# control-tu55v6.net
KiCad netlist of a schematic drawn in EAGLE
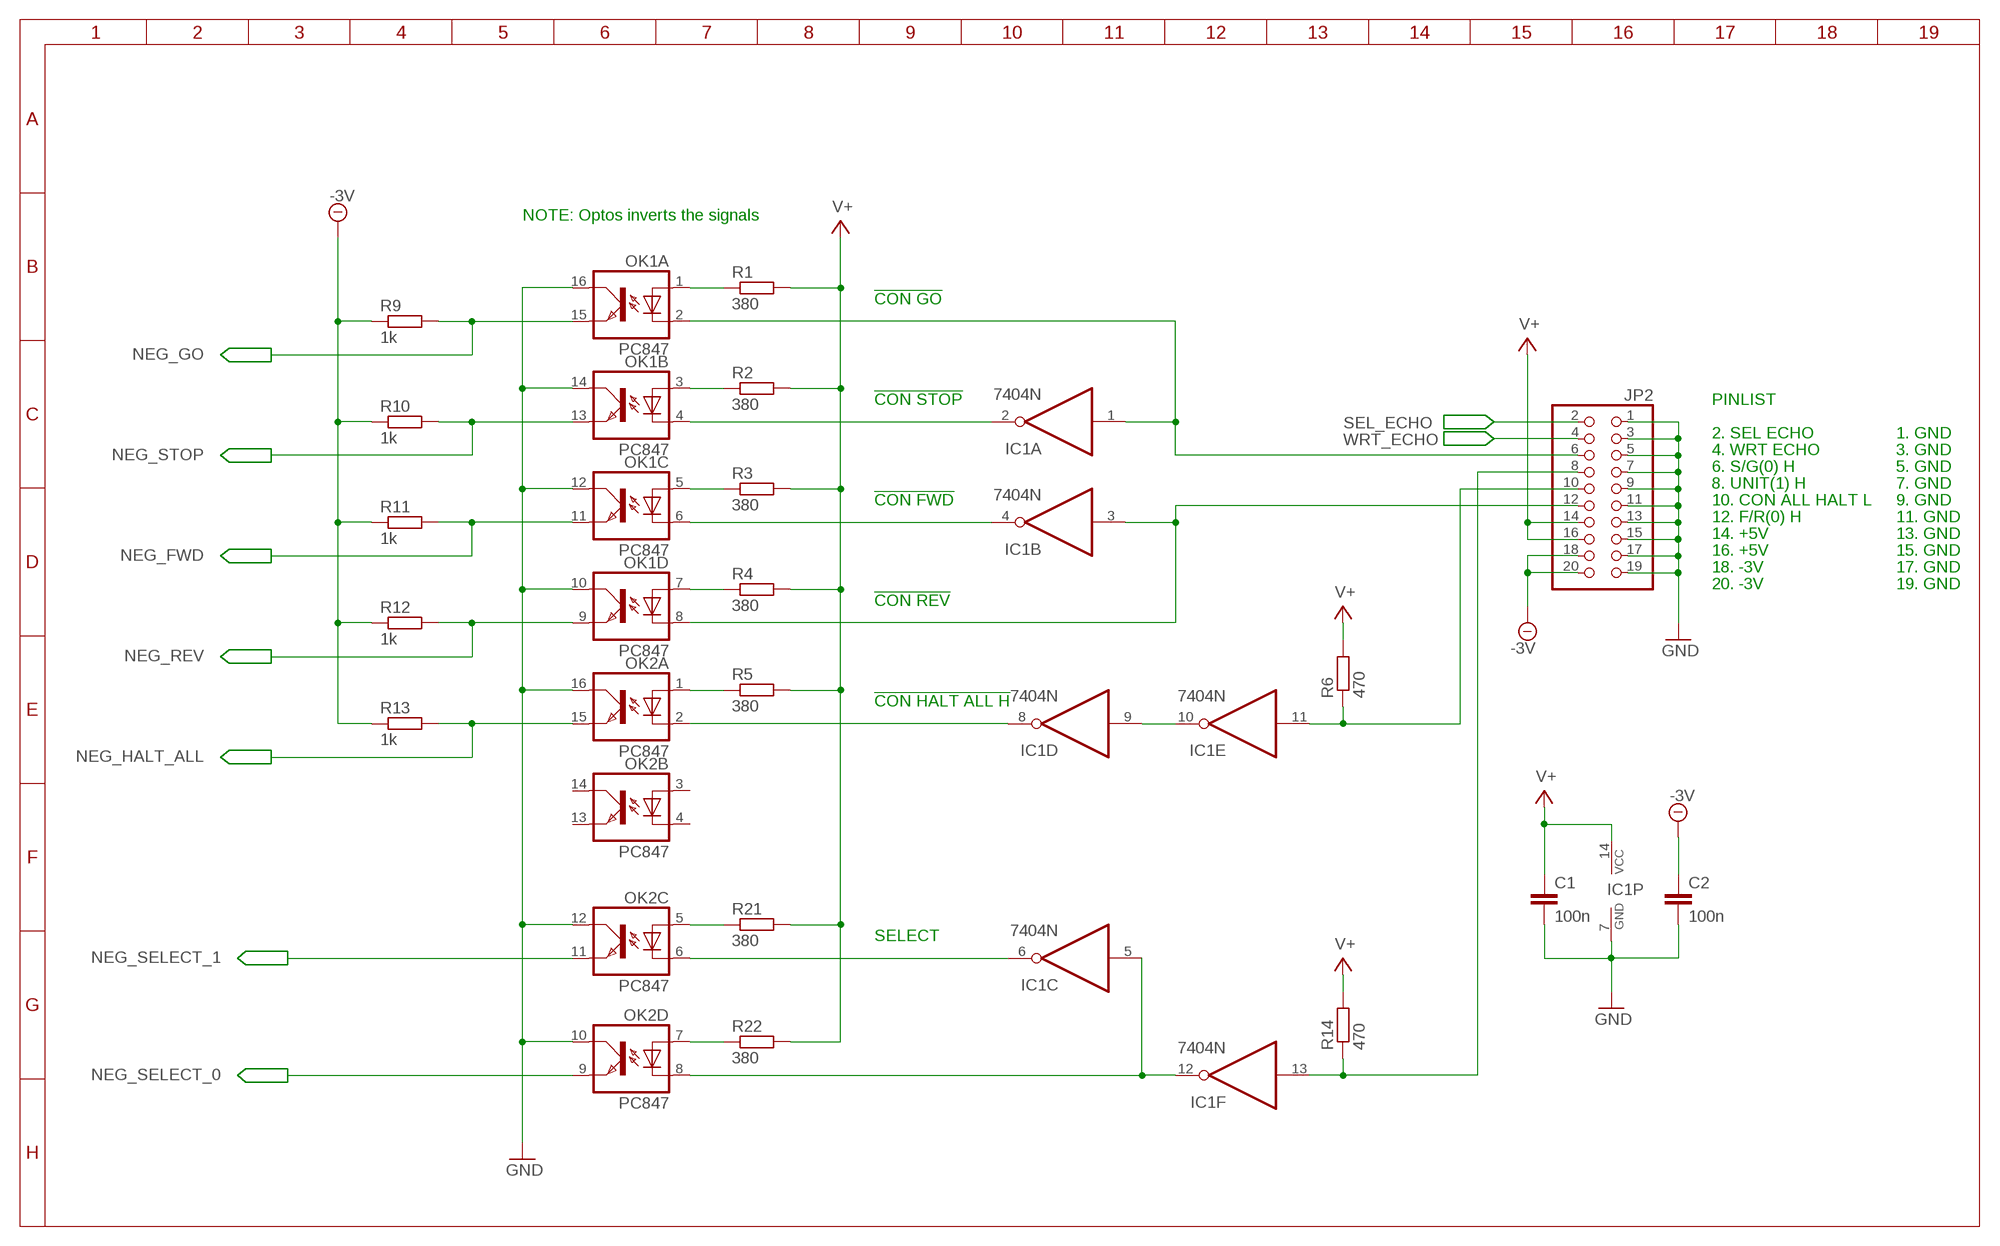
[diagram p0: schematic, sheet 1]
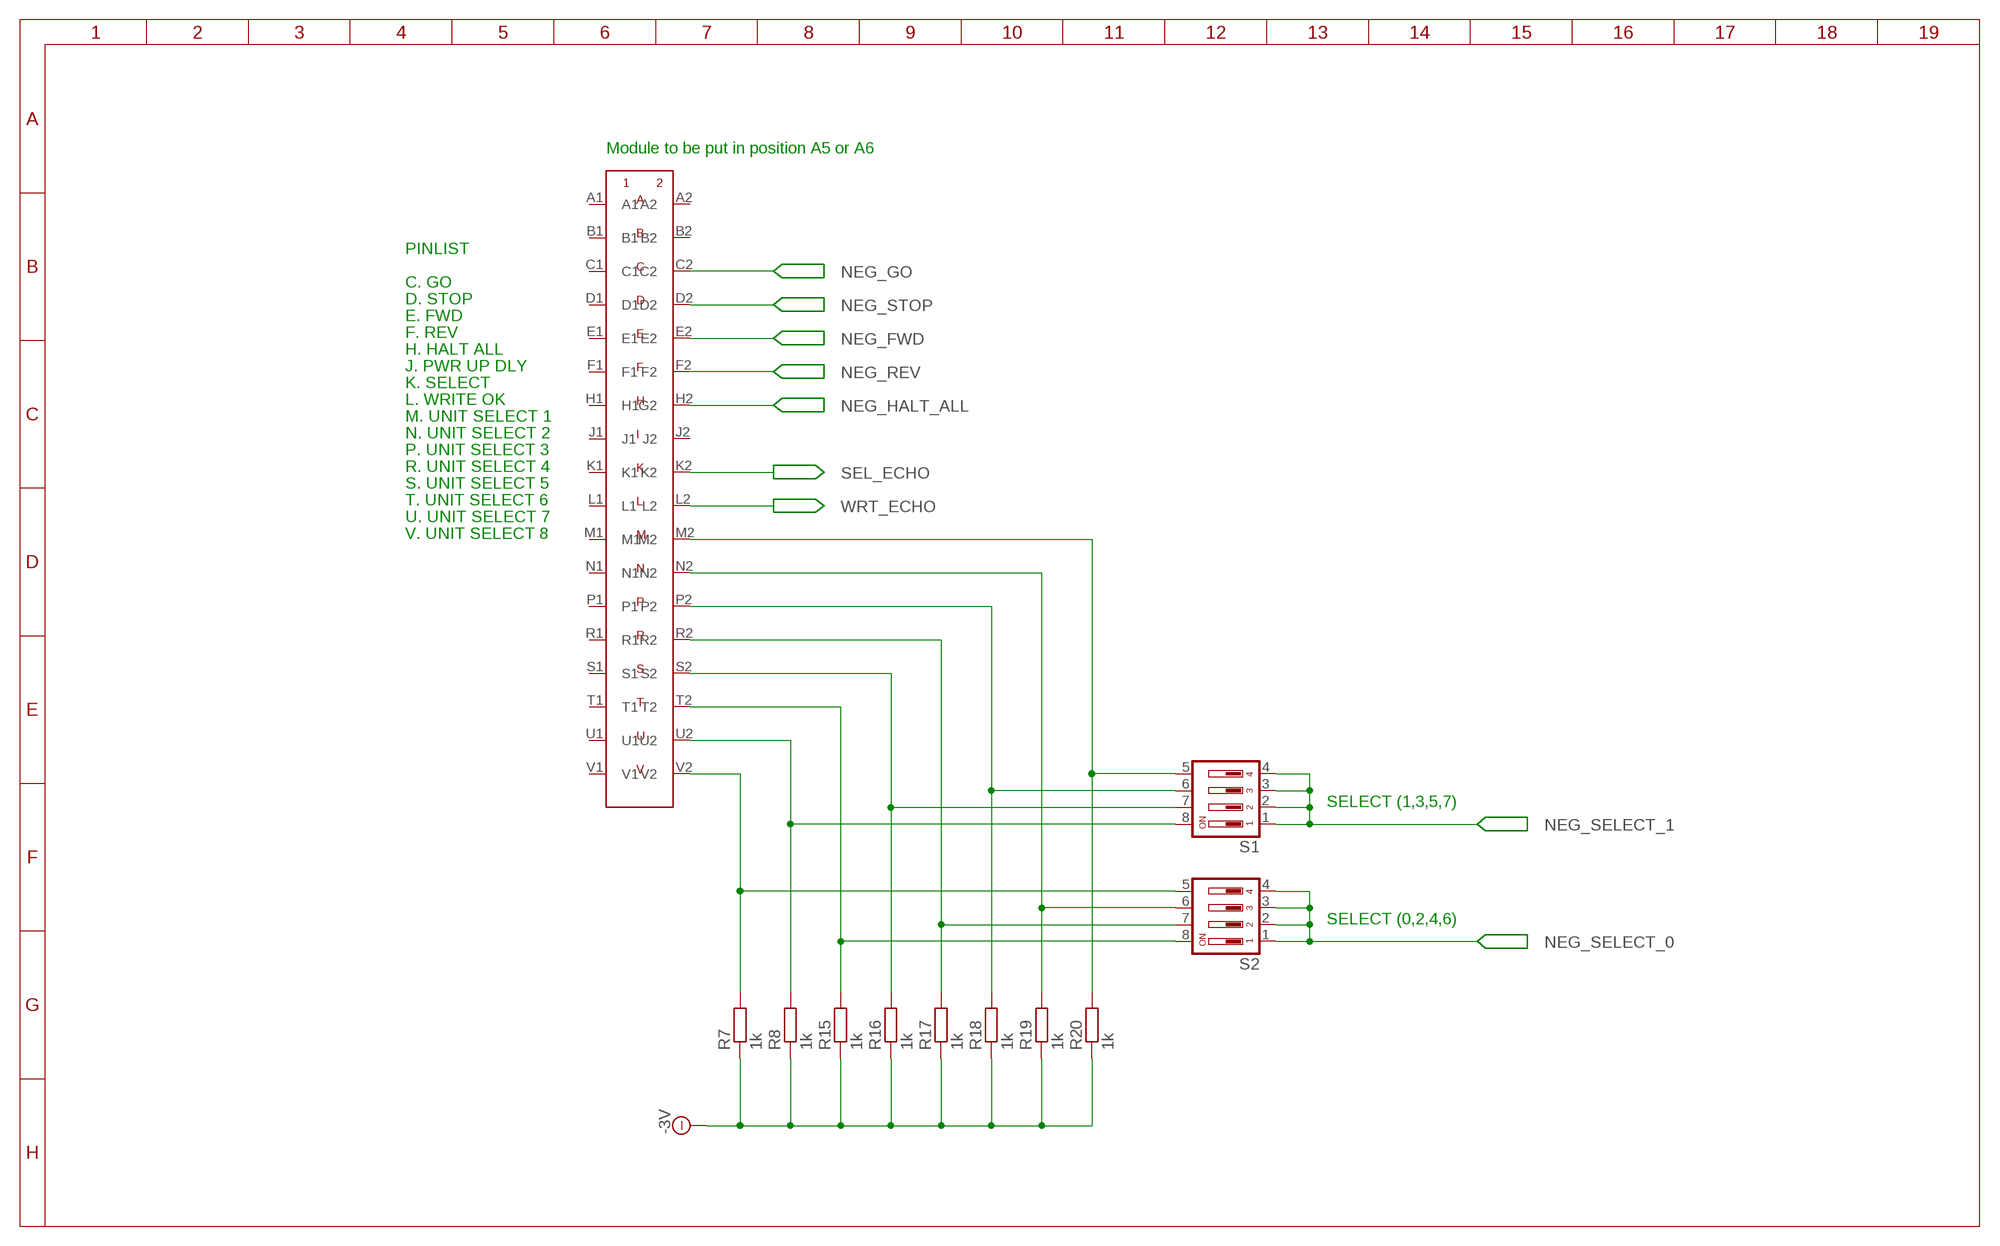
[diagram p1: schematic, sheet 2]

(export (version "E")
  (design (tool "Eeschema 10.0.6"))
  (components
    (comp (ref "C1")
      (value "100n")
      (footprint "eagle-import:C5B3.5")
      (libsource (lib "eagle-import") (part "C5/3.5"))
    )
    (comp (ref "C2")
      (value "100n")
      (footprint "eagle-import:C5B3.5")
      (libsource (lib "eagle-import") (part "C5/3.5"))
    )
    (comp (ref "IC1")
      (value "7404N")
      (footprint "eagle-import:DIL14")
      (libsource (lib "eagle-import") (part "7404N"))
    )
    (comp (ref "JP2")
      (value "PINHD-2X10/90-FRAMED")
      (footprint "eagle-import:2Z10_90-FRAMED")
      (libsource (lib "eagle-import") (part "PINHD-2X10/90-FRAMED"))
    )
    (comp (ref "OK1")
      (value "PC847")
      (footprint "eagle-import:DIL16")
      (libsource (lib "eagle-import") (part "PC847"))
    )
    (comp (ref "OK2")
      (value "PC847")
      (footprint "eagle-import:DIL16")
      (libsource (lib "eagle-import") (part "PC847"))
    )
    (comp (ref "R1")
      (value "380")
      (footprint "eagle-import:0207_10")
      (libsource (lib "eagle-import") (part "R-EU_0207/10"))
    )
    (comp (ref "R2")
      (value "380")
      (footprint "eagle-import:0207_10")
      (libsource (lib "eagle-import") (part "R-EU_0207/10"))
    )
    (comp (ref "R3")
      (value "380")
      (footprint "eagle-import:0207_10")
      (libsource (lib "eagle-import") (part "R-EU_0207/10"))
    )
    (comp (ref "R4")
      (value "380")
      (footprint "eagle-import:0207_10")
      (libsource (lib "eagle-import") (part "R-EU_0207/10"))
    )
    (comp (ref "R5")
      (value "380")
      (footprint "eagle-import:0207_10")
      (libsource (lib "eagle-import") (part "R-EU_0207/10"))
    )
    (comp (ref "R6")
      (value "470")
      (footprint "eagle-import:0207_10")
      (libsource (lib "eagle-import") (part "R-EU_0207/10"))
    )
    (comp (ref "R9")
      (value "1k")
      (footprint "eagle-import:0207_10")
      (libsource (lib "eagle-import") (part "R-EU_0207/10"))
    )
    (comp (ref "R10")
      (value "1k")
      (footprint "eagle-import:0207_10")
      (libsource (lib "eagle-import") (part "R-EU_0207/10"))
    )
    (comp (ref "R11")
      (value "1k")
      (footprint "eagle-import:0207_10")
      (libsource (lib "eagle-import") (part "R-EU_0207/10"))
    )
    (comp (ref "R12")
      (value "1k")
      (footprint "eagle-import:0207_10")
      (libsource (lib "eagle-import") (part "R-EU_0207/10"))
    )
    (comp (ref "R13")
      (value "1k")
      (footprint "eagle-import:0207_10")
      (libsource (lib "eagle-import") (part "R-EU_0207/10"))
    )
    (comp (ref "R14")
      (value "470")
      (footprint "eagle-import:0207_10")
      (libsource (lib "eagle-import") (part "R-EU_0207/10"))
    )
    (comp (ref "R21")
      (value "380")
      (footprint "eagle-import:0207_10")
      (libsource (lib "eagle-import") (part "R-EU_0207/10"))
    )
    (comp (ref "R22")
      (value "380")
      (footprint "eagle-import:0207_10")
      (libsource (lib "eagle-import") (part "R-EU_0207/10"))
    )
    (comp (ref "CON1")
      (value "FLIPCHIP_1NORMAL")
      (footprint "eagle-import:FLIPCHIP-1")
      (libsource (lib "eagle-import") (part "FLIPCHIP_1NORMAL"))
    )
    (comp (ref "R7")
      (value "1k")
      (footprint "eagle-import:0207_10")
      (libsource (lib "eagle-import") (part "R-EU_0207/10"))
    )
    (comp (ref "R8")
      (value "1k")
      (footprint "eagle-import:0207_10")
      (libsource (lib "eagle-import") (part "R-EU_0207/10"))
    )
    (comp (ref "R15")
      (value "1k")
      (footprint "eagle-import:0207_10")
      (libsource (lib "eagle-import") (part "R-EU_0207/10"))
    )
    (comp (ref "R16")
      (value "1k")
      (footprint "eagle-import:0207_10")
      (libsource (lib "eagle-import") (part "R-EU_0207/10"))
    )
    (comp (ref "R17")
      (value "1k")
      (footprint "eagle-import:0207_10")
      (libsource (lib "eagle-import") (part "R-EU_0207/10"))
    )
    (comp (ref "R18")
      (value "1k")
      (footprint "eagle-import:0207_10")
      (libsource (lib "eagle-import") (part "R-EU_0207/10"))
    )
    (comp (ref "R19")
      (value "1k")
      (footprint "eagle-import:0207_10")
      (libsource (lib "eagle-import") (part "R-EU_0207/10"))
    )
    (comp (ref "R20")
      (value "1k")
      (footprint "eagle-import:0207_10")
      (libsource (lib "eagle-import") (part "R-EU_0207/10"))
    )
    (comp (ref "S1")
      (value "DIP04YL")
      (footprint "eagle-import:DIP04YL")
      (libsource (lib "eagle-import") (part "DIP04YL"))
    )
    (comp (ref "S2")
      (value "DIP04YL")
      (footprint "eagle-import:DIP04YL")
      (libsource (lib "eagle-import") (part "DIP04YL"))
    )
  )
  (nets
    (net (code "1") (name "-3V") (class "Default")
      (node (ref "C2") (pin "1") (pinfunction "1_1") (pintype "passive"))
      (node (ref "JP2") (pin "18") (pinfunction "18_18") (pintype "passive"))
      (node (ref "JP2") (pin "20") (pinfunction "20_20") (pintype "passive"))
      (node (ref "R10") (pin "1") (pinfunction "1_1") (pintype "passive"))
      (node (ref "R11") (pin "1") (pinfunction "1_1") (pintype "passive"))
      (node (ref "R12") (pin "1") (pinfunction "1_1") (pintype "passive"))
      (node (ref "R13") (pin "1") (pinfunction "1_1") (pintype "passive"))
      (node (ref "R15") (pin "1") (pinfunction "1_1") (pintype "passive"))
      (node (ref "R16") (pin "1") (pinfunction "1_1") (pintype "passive"))
      (node (ref "R17") (pin "1") (pinfunction "1_1") (pintype "passive"))
      (node (ref "R18") (pin "1") (pinfunction "1_1") (pintype "passive"))
      (node (ref "R19") (pin "1") (pinfunction "1_1") (pintype "passive"))
      (node (ref "R20") (pin "1") (pinfunction "1_1") (pintype "passive"))
      (node (ref "R7") (pin "1") (pinfunction "1_1") (pintype "passive"))
      (node (ref "R8") (pin "1") (pinfunction "1_1") (pintype "passive"))
      (node (ref "R9") (pin "1") (pinfunction "1_1") (pintype "passive"))
    )
    (net (code "2") (name "GND") (class "Default")
      (node (ref "C1") (pin "2") (pinfunction "2_2") (pintype "passive"))
      (node (ref "C2") (pin "2") (pinfunction "2_2") (pintype "passive"))
      (node (ref "IC1") (pin "7") (pinfunction "GND_7") (pintype "power_in"))
      (node (ref "JP2") (pin "1") (pinfunction "1_1") (pintype "passive"))
      (node (ref "JP2") (pin "11") (pinfunction "11_11") (pintype "passive"))
      (node (ref "JP2") (pin "13") (pinfunction "13_13") (pintype "passive"))
      (node (ref "JP2") (pin "15") (pinfunction "15_15") (pintype "passive"))
      (node (ref "JP2") (pin "17") (pinfunction "17_17") (pintype "passive"))
      (node (ref "JP2") (pin "19") (pinfunction "19_19") (pintype "passive"))
      (node (ref "JP2") (pin "3") (pinfunction "3_3") (pintype "passive"))
      (node (ref "JP2") (pin "5") (pinfunction "5_5") (pintype "passive"))
      (node (ref "JP2") (pin "7") (pinfunction "7_7") (pintype "passive"))
      (node (ref "JP2") (pin "9") (pinfunction "9_9") (pintype "passive"))
      (node (ref "OK1") (pin "10") (pinfunction "COL_10") (pintype "passive"))
      (node (ref "OK1") (pin "12") (pinfunction "COL_12") (pintype "passive"))
      (node (ref "OK1") (pin "14") (pinfunction "COL_14") (pintype "passive"))
      (node (ref "OK1") (pin "16") (pinfunction "COL_16") (pintype "passive"))
      (node (ref "OK2") (pin "10") (pinfunction "COL_10") (pintype "passive"))
      (node (ref "OK2") (pin "12") (pinfunction "COL_12") (pintype "passive"))
      (node (ref "OK2") (pin "16") (pinfunction "COL_16") (pintype "passive"))
    )
    (net (code "3") (name "NEG_FWD") (class "Default")
      (node (ref "CON1") (pin "E2") (pinfunction "E2_E2") (pintype "bidirectional"))
      (node (ref "OK1") (pin "11") (pinfunction "EMIT_11") (pintype "passive"))
      (node (ref "R11") (pin "2") (pinfunction "2_2") (pintype "passive"))
    )
    (net (code "4") (name "NEG_GO") (class "Default")
      (node (ref "CON1") (pin "C2") (pinfunction "C2_C2") (pintype "bidirectional"))
      (node (ref "OK1") (pin "15") (pinfunction "EMIT_15") (pintype "passive"))
      (node (ref "R9") (pin "2") (pinfunction "2_2") (pintype "passive"))
    )
    (net (code "5") (name "NEG_HALT_ALL") (class "Default")
      (node (ref "CON1") (pin "H2") (pinfunction "G2_H2") (pintype "bidirectional"))
      (node (ref "OK2") (pin "15") (pinfunction "EMIT_15") (pintype "passive"))
      (node (ref "R13") (pin "2") (pinfunction "2_2") (pintype "passive"))
    )
    (net (code "6") (name "NEG_REV") (class "Default")
      (node (ref "CON1") (pin "F2") (pinfunction "F2_F2") (pintype "bidirectional"))
      (node (ref "OK1") (pin "9") (pinfunction "EMIT_9") (pintype "passive"))
      (node (ref "R12") (pin "2") (pinfunction "2_2") (pintype "passive"))
    )
    (net (code "7") (name "NEG_SELECT_0") (class "Default")
      (node (ref "OK2") (pin "9") (pinfunction "EMIT_9") (pintype "passive"))
      (node (ref "S2") (pin "1") (pinfunction "1_1") (pintype "passive"))
      (node (ref "S2") (pin "2") (pinfunction "2_2") (pintype "passive"))
      (node (ref "S2") (pin "3") (pinfunction "3_3") (pintype "passive"))
      (node (ref "S2") (pin "4") (pinfunction "4_4") (pintype "passive"))
    )
    (net (code "8") (name "NEG_SELECT_1") (class "Default")
      (node (ref "OK2") (pin "11") (pinfunction "EMIT_11") (pintype "passive"))
      (node (ref "S1") (pin "1") (pinfunction "1_1") (pintype "passive"))
      (node (ref "S1") (pin "2") (pinfunction "2_2") (pintype "passive"))
      (node (ref "S1") (pin "3") (pinfunction "3_3") (pintype "passive"))
      (node (ref "S1") (pin "4") (pinfunction "4_4") (pintype "passive"))
    )
    (net (code "9") (name "NEG_STOP") (class "Default")
      (node (ref "CON1") (pin "D2") (pinfunction "D2_D2") (pintype "bidirectional"))
      (node (ref "OK1") (pin "13") (pinfunction "EMIT_13") (pintype "passive"))
      (node (ref "R10") (pin "2") (pinfunction "2_2") (pintype "passive"))
    )
    (net (code "10") (name "Net-(CON1-PadM2)") (class "Default")
      (node (ref "CON1") (pin "M2") (pinfunction "M2_M2") (pintype "bidirectional"))
      (node (ref "R20") (pin "2") (pinfunction "2_2") (pintype "passive"))
      (node (ref "S1") (pin "5") (pinfunction "5_5") (pintype "passive"))
    )
    (net (code "11") (name "Net-(CON1-PadN2)") (class "Default")
      (node (ref "CON1") (pin "N2") (pinfunction "N2_N2") (pintype "bidirectional"))
      (node (ref "R19") (pin "2") (pinfunction "2_2") (pintype "passive"))
      (node (ref "S2") (pin "6") (pinfunction "6_6") (pintype "passive"))
    )
    (net (code "12") (name "Net-(CON1-PadP2)") (class "Default")
      (node (ref "CON1") (pin "P2") (pinfunction "P2_P2") (pintype "bidirectional"))
      (node (ref "R18") (pin "2") (pinfunction "2_2") (pintype "passive"))
      (node (ref "S1") (pin "6") (pinfunction "6_6") (pintype "passive"))
    )
    (net (code "13") (name "Net-(CON1-PadR2)") (class "Default")
      (node (ref "CON1") (pin "R2") (pinfunction "R2_R2") (pintype "bidirectional"))
      (node (ref "R17") (pin "2") (pinfunction "2_2") (pintype "passive"))
      (node (ref "S2") (pin "7") (pinfunction "7_7") (pintype "passive"))
    )
    (net (code "14") (name "Net-(CON1-PadS2)") (class "Default")
      (node (ref "CON1") (pin "S2") (pinfunction "S2_S2") (pintype "bidirectional"))
      (node (ref "R16") (pin "2") (pinfunction "2_2") (pintype "passive"))
      (node (ref "S1") (pin "7") (pinfunction "7_7") (pintype "passive"))
    )
    (net (code "15") (name "Net-(CON1-PadT2)") (class "Default")
      (node (ref "CON1") (pin "T2") (pinfunction "T2_T2") (pintype "bidirectional"))
      (node (ref "R15") (pin "2") (pinfunction "2_2") (pintype "passive"))
      (node (ref "S2") (pin "8") (pinfunction "8_8") (pintype "passive"))
    )
    (net (code "16") (name "Net-(CON1-PadU2)") (class "Default")
      (node (ref "CON1") (pin "U2") (pinfunction "U2_U2") (pintype "bidirectional"))
      (node (ref "R8") (pin "2") (pinfunction "2_2") (pintype "passive"))
      (node (ref "S1") (pin "8") (pinfunction "8_8") (pintype "passive"))
    )
    (net (code "17") (name "Net-(CON1-PadV2)") (class "Default")
      (node (ref "CON1") (pin "V2") (pinfunction "V2_V2") (pintype "bidirectional"))
      (node (ref "R7") (pin "2") (pinfunction "2_2") (pintype "passive"))
      (node (ref "S2") (pin "5") (pinfunction "5_5") (pintype "passive"))
    )
    (net (code "18") (name "Net-(IC1A-I)") (class "Default")
      (node (ref "IC1") (pin "1") (pinfunction "I_1") (pintype "input"))
      (node (ref "JP2") (pin "6") (pinfunction "6_6") (pintype "passive"))
      (node (ref "OK1") (pin "2") (pinfunction "C_2") (pintype "passive"))
    )
    (net (code "19") (name "Net-(IC1A-O)") (class "Default")
      (node (ref "IC1") (pin "2") (pinfunction "O_2") (pintype "output"))
      (node (ref "OK1") (pin "4") (pinfunction "C_4") (pintype "passive"))
    )
    (net (code "20") (name "Net-(IC1B-I)") (class "Default")
      (node (ref "IC1") (pin "3") (pinfunction "I_3") (pintype "input"))
      (node (ref "JP2") (pin "12") (pinfunction "12_12") (pintype "passive"))
      (node (ref "OK1") (pin "8") (pinfunction "C_8") (pintype "passive"))
    )
    (net (code "21") (name "Net-(IC1B-O)") (class "Default")
      (node (ref "IC1") (pin "4") (pinfunction "O_4") (pintype "output"))
      (node (ref "OK1") (pin "6") (pinfunction "C_6") (pintype "passive"))
    )
    (net (code "22") (name "Net-(IC1C-I)") (class "Default")
      (node (ref "IC1") (pin "12") (pinfunction "O_12") (pintype "output"))
      (node (ref "IC1") (pin "5") (pinfunction "I_5") (pintype "input"))
      (node (ref "OK2") (pin "8") (pinfunction "C_8") (pintype "passive"))
    )
    (net (code "23") (name "Net-(IC1C-O)") (class "Default")
      (node (ref "IC1") (pin "6") (pinfunction "O_6") (pintype "output"))
      (node (ref "OK2") (pin "6") (pinfunction "C_6") (pintype "passive"))
    )
    (net (code "24") (name "Net-(IC1D-I)") (class "Default")
      (node (ref "IC1") (pin "10") (pinfunction "O_10") (pintype "output"))
      (node (ref "IC1") (pin "9") (pinfunction "I_9") (pintype "input"))
    )
    (net (code "25") (name "Net-(IC1D-O)") (class "Default")
      (node (ref "IC1") (pin "8") (pinfunction "O_8") (pintype "output"))
      (node (ref "OK2") (pin "2") (pinfunction "C_2") (pintype "passive"))
    )
    (net (code "26") (name "Net-(IC1E-I)") (class "Default")
      (node (ref "IC1") (pin "11") (pinfunction "I_11") (pintype "input"))
      (node (ref "JP2") (pin "10") (pinfunction "10_10") (pintype "passive"))
      (node (ref "R6") (pin "1") (pinfunction "1_1") (pintype "passive"))
    )
    (net (code "27") (name "Net-(IC1F-I)") (class "Default")
      (node (ref "IC1") (pin "13") (pinfunction "I_13") (pintype "input"))
      (node (ref "JP2") (pin "8") (pinfunction "8_8") (pintype "passive"))
      (node (ref "R14") (pin "1") (pinfunction "1_1") (pintype "passive"))
    )
    (net (code "28") (name "Net-(OK1A-A)") (class "Default")
      (node (ref "OK1") (pin "1") (pinfunction "A_1") (pintype "passive"))
      (node (ref "R1") (pin "1") (pinfunction "1_1") (pintype "passive"))
    )
    (net (code "29") (name "Net-(OK1B-A)") (class "Default")
      (node (ref "OK1") (pin "3") (pinfunction "A_3") (pintype "passive"))
      (node (ref "R2") (pin "1") (pinfunction "1_1") (pintype "passive"))
    )
    (net (code "30") (name "Net-(OK1C-A)") (class "Default")
      (node (ref "OK1") (pin "5") (pinfunction "A_5") (pintype "passive"))
      (node (ref "R3") (pin "1") (pinfunction "1_1") (pintype "passive"))
    )
    (net (code "31") (name "Net-(OK1D-A)") (class "Default")
      (node (ref "OK1") (pin "7") (pinfunction "A_7") (pintype "passive"))
      (node (ref "R4") (pin "1") (pinfunction "1_1") (pintype "passive"))
    )
    (net (code "32") (name "Net-(OK2A-A)") (class "Default")
      (node (ref "OK2") (pin "1") (pinfunction "A_1") (pintype "passive"))
      (node (ref "R5") (pin "1") (pinfunction "1_1") (pintype "passive"))
    )
    (net (code "33") (name "Net-(OK2C-A)") (class "Default")
      (node (ref "OK2") (pin "5") (pinfunction "A_5") (pintype "passive"))
      (node (ref "R21") (pin "1") (pinfunction "1_1") (pintype "passive"))
    )
    (net (code "34") (name "Net-(OK2D-A)") (class "Default")
      (node (ref "OK2") (pin "7") (pinfunction "A_7") (pintype "passive"))
      (node (ref "R22") (pin "1") (pinfunction "1_1") (pintype "passive"))
    )
    (net (code "35") (name "SEL_ECHO") (class "Default")
      (node (ref "CON1") (pin "K2") (pinfunction "K2_K2") (pintype "bidirectional"))
      (node (ref "JP2") (pin "2") (pinfunction "2_2") (pintype "passive"))
    )
    (net (code "36") (name "V+") (class "Default")
      (node (ref "C1") (pin "1") (pinfunction "1_1") (pintype "passive"))
      (node (ref "IC1") (pin "14") (pinfunction "VCC_14") (pintype "power_in"))
      (node (ref "JP2") (pin "14") (pinfunction "14_14") (pintype "passive"))
      (node (ref "JP2") (pin "16") (pinfunction "16_16") (pintype "passive"))
      (node (ref "R1") (pin "2") (pinfunction "2_2") (pintype "passive"))
      (node (ref "R14") (pin "2") (pinfunction "2_2") (pintype "passive"))
      (node (ref "R2") (pin "2") (pinfunction "2_2") (pintype "passive"))
      (node (ref "R21") (pin "2") (pinfunction "2_2") (pintype "passive"))
      (node (ref "R22") (pin "2") (pinfunction "2_2") (pintype "passive"))
      (node (ref "R3") (pin "2") (pinfunction "2_2") (pintype "passive"))
      (node (ref "R4") (pin "2") (pinfunction "2_2") (pintype "passive"))
      (node (ref "R5") (pin "2") (pinfunction "2_2") (pintype "passive"))
      (node (ref "R6") (pin "2") (pinfunction "2_2") (pintype "passive"))
    )
    (net (code "37") (name "WRT_ECHO") (class "Default")
      (node (ref "CON1") (pin "L2") (pinfunction "L2_L2") (pintype "bidirectional"))
      (node (ref "JP2") (pin "4") (pinfunction "4_4") (pintype "passive"))
    )
    (net (code "38") (name "unconnected-(CON1-PadA1)") (class "Default")
      (node (ref "CON1") (pin "A1") (pinfunction "A1_A1") (pintype "bidirectional"))
    )
    (net (code "39") (name "unconnected-(CON1-PadA2)") (class "Default")
      (node (ref "CON1") (pin "A2") (pinfunction "A2_A2") (pintype "bidirectional"))
    )
    (net (code "40") (name "unconnected-(CON1-PadB1)") (class "Default")
      (node (ref "CON1") (pin "B1") (pinfunction "B1_B1") (pintype "bidirectional"))
    )
    (net (code "41") (name "unconnected-(CON1-PadB2)") (class "Default")
      (node (ref "CON1") (pin "B2") (pinfunction "B2_B2") (pintype "bidirectional"))
    )
    (net (code "42") (name "unconnected-(CON1-PadC1)") (class "Default")
      (node (ref "CON1") (pin "C1") (pinfunction "C1_C1") (pintype "bidirectional"))
    )
    (net (code "43") (name "unconnected-(CON1-PadD1)") (class "Default")
      (node (ref "CON1") (pin "D1") (pinfunction "D1_D1") (pintype "bidirectional"))
    )
    (net (code "44") (name "unconnected-(CON1-PadE1)") (class "Default")
      (node (ref "CON1") (pin "E1") (pinfunction "E1_E1") (pintype "bidirectional"))
    )
    (net (code "45") (name "unconnected-(CON1-PadF1)") (class "Default")
      (node (ref "CON1") (pin "F1") (pinfunction "F1_F1") (pintype "bidirectional"))
    )
    (net (code "46") (name "unconnected-(CON1-PadH1)") (class "Default")
      (node (ref "CON1") (pin "H1") (pinfunction "H1_H1") (pintype "bidirectional"))
    )
    (net (code "47") (name "unconnected-(CON1-PadJ1)") (class "Default")
      (node (ref "CON1") (pin "J1") (pinfunction "J1_J1") (pintype "bidirectional"))
    )
    (net (code "48") (name "unconnected-(CON1-PadJ2)") (class "Default")
      (node (ref "CON1") (pin "J2") (pinfunction "J2_J2") (pintype "bidirectional"))
    )
    (net (code "49") (name "unconnected-(CON1-PadK1)") (class "Default")
      (node (ref "CON1") (pin "K1") (pinfunction "K1_K1") (pintype "bidirectional"))
    )
    (net (code "50") (name "unconnected-(CON1-PadL1)") (class "Default")
      (node (ref "CON1") (pin "L1") (pinfunction "L1_L1") (pintype "bidirectional"))
    )
    (net (code "51") (name "unconnected-(CON1-PadM1)") (class "Default")
      (node (ref "CON1") (pin "M1") (pinfunction "M1_M1") (pintype "bidirectional"))
    )
    (net (code "52") (name "unconnected-(CON1-PadN1)") (class "Default")
      (node (ref "CON1") (pin "N1") (pinfunction "N1_N1") (pintype "bidirectional"))
    )
    (net (code "53") (name "unconnected-(CON1-PadP1)") (class "Default")
      (node (ref "CON1") (pin "P1") (pinfunction "P1_P1") (pintype "bidirectional"))
    )
    (net (code "54") (name "unconnected-(CON1-PadR1)") (class "Default")
      (node (ref "CON1") (pin "R1") (pinfunction "R1_R1") (pintype "bidirectional"))
    )
    (net (code "55") (name "unconnected-(CON1-PadS1)") (class "Default")
      (node (ref "CON1") (pin "S1") (pinfunction "S1_S1") (pintype "bidirectional"))
    )
    (net (code "56") (name "unconnected-(CON1-PadT1)") (class "Default")
      (node (ref "CON1") (pin "T1") (pinfunction "T1_T1") (pintype "bidirectional"))
    )
    (net (code "57") (name "unconnected-(CON1-PadU1)") (class "Default")
      (node (ref "CON1") (pin "U1") (pinfunction "U1_U1") (pintype "bidirectional"))
    )
    (net (code "58") (name "unconnected-(CON1-PadV1)") (class "Default")
      (node (ref "CON1") (pin "V1") (pinfunction "V1_V1") (pintype "bidirectional"))
    )
    (net (code "59") (name "unconnected-(OK2B-A-Pad3)") (class "Default")
      (node (ref "OK2") (pin "3") (pinfunction "A_3") (pintype "passive"))
    )
    (net (code "60") (name "unconnected-(OK2B-C-Pad4)") (class "Default")
      (node (ref "OK2") (pin "4") (pinfunction "C_4") (pintype "passive"))
    )
    (net (code "61") (name "unconnected-(OK2B-COL-Pad14)") (class "Default")
      (node (ref "OK2") (pin "14") (pinfunction "COL_14") (pintype "passive"))
    )
    (net (code "62") (name "unconnected-(OK2B-EMIT-Pad13)") (class "Default")
      (node (ref "OK2") (pin "13") (pinfunction "EMIT_13") (pintype "passive"))
    )
  )
)
